# 03-CameraSensor.net
KiCad netlist of a schematic drawn in Altium Designer
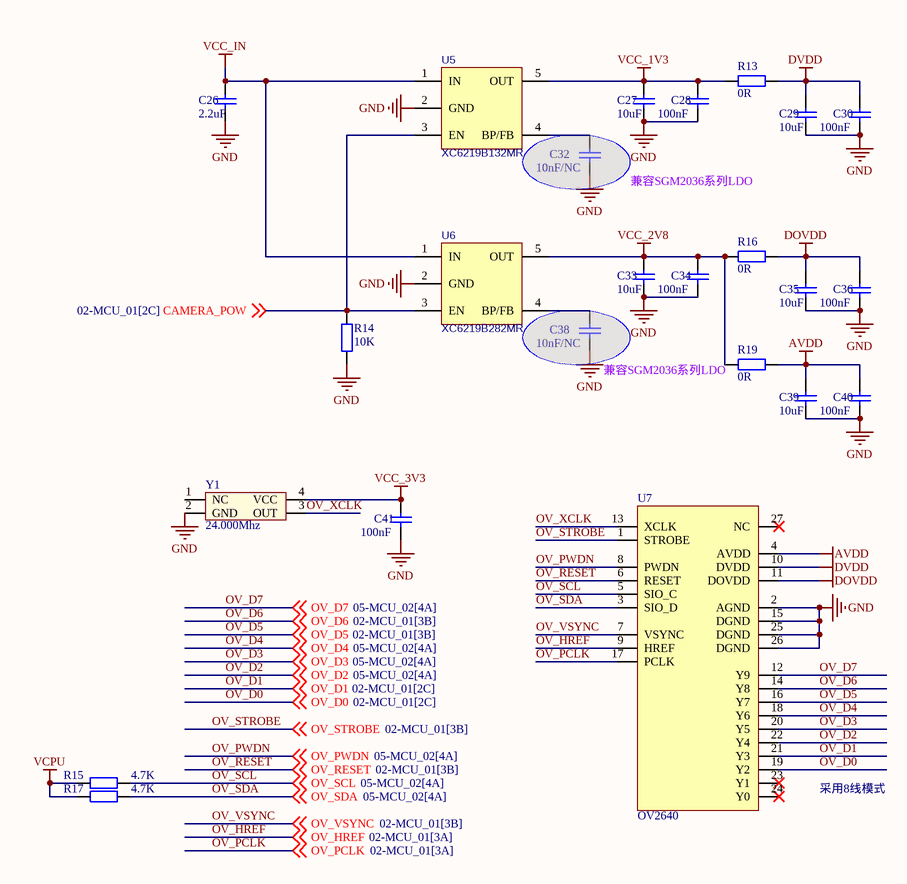
[diagram p0: 03-CameraSensor.SchDoc]

(export (version "E")
  (design (tool "Eeschema 10.0.6"))
  (components
    (comp (ref "C26")
      (value "2.2uF")
      (footprint "C0603_M")
      (description "贴片电容/MLCC电容")
      (libsource (lib "0.1 - 电阻-电容-电感-保险丝-晶振-晶体-磁珠-电位器-法拉电容-馈通电容") (part "C"))
    )
    (comp (ref "C27")
      (value "10uF")
      (footprint "C0603_M")
      (description "贴片电容/MLCC电容")
      (libsource (lib "0.1 - 电阻-电容-电感-保险丝-晶振-晶体-磁珠-电位器-法拉电容-馈通电容") (part "C"))
    )
    (comp (ref "C28")
      (value "100nF")
      (footprint "C0603_M")
      (description "贴片电容/MLCC电容")
      (libsource (lib "0.1 - 电阻-电容-电感-保险丝-晶振-晶体-磁珠-电位器-法拉电容-馈通电容") (part "C"))
    )
    (comp (ref "C29")
      (value "10uF")
      (footprint "C0603_M")
      (description "贴片电容/MLCC电容")
      (libsource (lib "0.1 - 电阻-电容-电感-保险丝-晶振-晶体-磁珠-电位器-法拉电容-馈通电容") (part "C"))
    )
    (comp (ref "C30")
      (value "100nF")
      (footprint "C0603_M")
      (description "贴片电容/MLCC电容")
      (libsource (lib "0.1 - 电阻-电容-电感-保险丝-晶振-晶体-磁珠-电位器-法拉电容-馈通电容") (part "C"))
    )
    (comp (ref "C32")
      (value "10nF/NC")
      (footprint "C0603_M")
      (description "贴片电容/MLCC电容")
      (libsource (lib "0.1 - 电阻-电容-电感-保险丝-晶振-晶体-磁珠-电位器-法拉电容-馈通电容") (part "C"))
    )
    (comp (ref "C33")
      (value "10uF")
      (footprint "C0603_M")
      (description "贴片电容/MLCC电容")
      (libsource (lib "0.1 - 电阻-电容-电感-保险丝-晶振-晶体-磁珠-电位器-法拉电容-馈通电容") (part "C"))
    )
    (comp (ref "C34")
      (value "100nF")
      (footprint "C0603_M")
      (description "贴片电容/MLCC电容")
      (libsource (lib "0.1 - 电阻-电容-电感-保险丝-晶振-晶体-磁珠-电位器-法拉电容-馈通电容") (part "C"))
    )
    (comp (ref "C35")
      (value "10uF")
      (footprint "C0603_M")
      (description "贴片电容/MLCC电容")
      (libsource (lib "0.1 - 电阻-电容-电感-保险丝-晶振-晶体-磁珠-电位器-法拉电容-馈通电容") (part "C"))
    )
    (comp (ref "C36")
      (value "100nF")
      (footprint "C0603_M")
      (description "贴片电容/MLCC电容")
      (libsource (lib "0.1 - 电阻-电容-电感-保险丝-晶振-晶体-磁珠-电位器-法拉电容-馈通电容") (part "C"))
    )
    (comp (ref "C38")
      (value "10nF/NC")
      (footprint "C0603_M")
      (description "贴片电容/MLCC电容")
      (libsource (lib "0.1 - 电阻-电容-电感-保险丝-晶振-晶体-磁珠-电位器-法拉电容-馈通电容") (part "C"))
    )
    (comp (ref "C39")
      (value "10uF")
      (footprint "C0603_M")
      (description "贴片电容/MLCC电容")
      (libsource (lib "0.1 - 电阻-电容-电感-保险丝-晶振-晶体-磁珠-电位器-法拉电容-馈通电容") (part "C"))
    )
    (comp (ref "C40")
      (value "100nF")
      (footprint "C0603_M")
      (description "贴片电容/MLCC电容")
      (libsource (lib "0.1 - 电阻-电容-电感-保险丝-晶振-晶体-磁珠-电位器-法拉电容-馈通电容") (part "C"))
    )
    (comp (ref "C41")
      (value "100nF")
      (footprint "C0603_M")
      (description "贴片电容/MLCC电容")
      (libsource (lib "0.1 - 电阻-电容-电感-保险丝-晶振-晶体-磁珠-电位器-法拉电容-馈通电容") (part "C"))
    )
    (comp (ref "R13")
      (value "0R")
      (footprint "R0603_M")
      (description "贴片电阻")
      (libsource (lib "0.1 - 电阻-电容-电感-保险丝-晶振-晶体-磁珠-电位器-法拉电容-馈通电容") (part "R"))
    )
    (comp (ref "R14")
      (value "10K")
      (footprint "R0603_M")
      (description "贴片电阻")
      (libsource (lib "0.1 - 电阻-电容-电感-保险丝-晶振-晶体-磁珠-电位器-法拉电容-馈通电容") (part "R"))
    )
    (comp (ref "R15")
      (value "4.7K")
      (footprint "R0402_M")
      (description "贴片电阻")
      (libsource (lib "0.1 - 电阻-电容-电感-保险丝-晶振-晶体-磁珠-电位器-法拉电容-馈通电容") (part "R"))
    )
    (comp (ref "R16")
      (value "0R")
      (footprint "R0603_M")
      (description "贴片电阻")
      (libsource (lib "0.1 - 电阻-电容-电感-保险丝-晶振-晶体-磁珠-电位器-法拉电容-馈通电容") (part "R"))
    )
    (comp (ref "R17")
      (value "4.7K")
      (footprint "R0402_M")
      (description "贴片电阻")
      (libsource (lib "0.1 - 电阻-电容-电感-保险丝-晶振-晶体-磁珠-电位器-法拉电容-馈通电容") (part "R"))
    )
    (comp (ref "R19")
      (value "0R")
      (footprint "R0603_M")
      (description "贴片电阻")
      (libsource (lib "0.1 - 电阻-电容-电感-保险丝-晶振-晶体-磁珠-电位器-法拉电容-馈通电容") (part "R"))
    )
    (comp (ref "U5")
      (value "XC6219B132MR")
      (footprint "SOT-23-5")
      (description "LDO 1.8V/0.3A")
      (libsource (lib "0.7 - 电源类芯片") (part "SGM2019-1.8YN5G"))
    )
    (comp (ref "U6")
      (value "XC6219B282MR")
      (footprint "SOT-23-5")
      (description "LDO 1.8V/0.3A")
      (libsource (lib "0.7 - 电源类芯片") (part "SGM2019-1.8YN5G"))
    )
    (comp (ref "U7")
      (value "OV2640")
      (footprint "OV2640-24")
      (libsource (lib "ATK-OV2640 V2.2") (part "OV2640"))
    )
    (comp (ref "Y1")
      (value "24.000Mhz")
      (footprint "XTAL3225")
      (description "有源晶振")
      (libsource (lib "ATK-OV2640 V2.2") (part "XTAL_S"))
    )
  )
  (nets
    (net (code "1") (name "/OV_XCLK") (class "Default")
      (node (ref "U7") (pin "13") (pinfunction "XCLK_13") (pintype "passive"))
      (node (ref "Y1") (pin "3") (pinfunction "OUT_3") (pintype "passive"))
    )
    (net (code "2") (name "AVDD") (class "Default")
      (node (ref "C39") (pin "2") (pinfunction "2_2") (pintype "passive"))
      (node (ref "C40") (pin "2") (pinfunction "2_2") (pintype "passive"))
      (node (ref "R19") (pin "2") (pinfunction "2_2") (pintype "passive"))
      (node (ref "U7") (pin "4") (pinfunction "AVDD_4") (pintype "passive"))
    )
    (net (code "3") (name "CAMERA_POW") (class "Default")
      (node (ref "R14") (pin "2") (pinfunction "2_2") (pintype "passive"))
      (node (ref "U5") (pin "3") (pinfunction "EN_3") (pintype "passive"))
      (node (ref "U6") (pin "3") (pinfunction "EN_3") (pintype "passive"))
    )
    (net (code "4") (name "DOVDD") (class "Default")
      (node (ref "C35") (pin "2") (pinfunction "2_2") (pintype "passive"))
      (node (ref "C36") (pin "2") (pinfunction "2_2") (pintype "passive"))
      (node (ref "R16") (pin "2") (pinfunction "2_2") (pintype "passive"))
      (node (ref "U7") (pin "11") (pinfunction "DOVDD_11") (pintype "passive"))
    )
    (net (code "5") (name "DVDD") (class "Default")
      (node (ref "C29") (pin "2") (pinfunction "2_2") (pintype "passive"))
      (node (ref "C30") (pin "2") (pinfunction "2_2") (pintype "passive"))
      (node (ref "R13") (pin "2") (pinfunction "2_2") (pintype "passive"))
      (node (ref "U7") (pin "10") (pinfunction "DVDD_10") (pintype "passive"))
    )
    (net (code "6") (name "GND") (class "Default")
      (node (ref "C26") (pin "1") (pinfunction "1_1") (pintype "passive"))
      (node (ref "C27") (pin "1") (pinfunction "1_1") (pintype "passive"))
      (node (ref "C28") (pin "1") (pinfunction "1_1") (pintype "passive"))
      (node (ref "C29") (pin "1") (pinfunction "1_1") (pintype "passive"))
      (node (ref "C30") (pin "1") (pinfunction "1_1") (pintype "passive"))
      (node (ref "C32") (pin "1") (pinfunction "1_1") (pintype "passive"))
      (node (ref "C33") (pin "1") (pinfunction "1_1") (pintype "passive"))
      (node (ref "C34") (pin "1") (pinfunction "1_1") (pintype "passive"))
      (node (ref "C35") (pin "1") (pinfunction "1_1") (pintype "passive"))
      (node (ref "C36") (pin "1") (pinfunction "1_1") (pintype "passive"))
      (node (ref "C38") (pin "1") (pinfunction "1_1") (pintype "passive"))
      (node (ref "C39") (pin "1") (pinfunction "1_1") (pintype "passive"))
      (node (ref "C40") (pin "1") (pinfunction "1_1") (pintype "passive"))
      (node (ref "C41") (pin "1") (pinfunction "1_1") (pintype "passive"))
      (node (ref "R14") (pin "1") (pinfunction "1_1") (pintype "passive"))
      (node (ref "U5") (pin "2") (pinfunction "GND_2") (pintype "passive"))
      (node (ref "U6") (pin "2") (pinfunction "GND_2") (pintype "passive"))
      (node (ref "U7") (pin "15") (pinfunction "DGND_15") (pintype "passive"))
      (node (ref "U7") (pin "2") (pinfunction "AGND_2") (pintype "passive"))
      (node (ref "U7") (pin "25") (pinfunction "DGND_25") (pintype "passive"))
      (node (ref "U7") (pin "26") (pinfunction "DGND_26") (pintype "passive"))
      (node (ref "Y1") (pin "2") (pinfunction "GND_2") (pintype "passive"))
    )
    (net (code "7") (name "Net-(U5-BP{slash}FB)") (class "Default")
      (node (ref "C32") (pin "2") (pinfunction "2_2") (pintype "passive"))
      (node (ref "U5") (pin "4") (pinfunction "BP/FB_4") (pintype "passive"))
    )
    (net (code "8") (name "Net-(U6-BP{slash}FB)") (class "Default")
      (node (ref "C38") (pin "2") (pinfunction "2_2") (pintype "passive"))
      (node (ref "U6") (pin "4") (pinfunction "BP/FB_4") (pintype "passive"))
    )
    (net (code "9") (name "OV_D0") (class "Default")
      (node (ref "U7") (pin "19") (pinfunction "Y2_19") (pintype "passive"))
    )
    (net (code "10") (name "OV_D1") (class "Default")
      (node (ref "U7") (pin "21") (pinfunction "Y3_21") (pintype "passive"))
    )
    (net (code "11") (name "OV_D2") (class "Default")
      (node (ref "U7") (pin "22") (pinfunction "Y4_22") (pintype "passive"))
    )
    (net (code "12") (name "OV_D3") (class "Default")
      (node (ref "U7") (pin "20") (pinfunction "Y5_20") (pintype "passive"))
    )
    (net (code "13") (name "OV_D4") (class "Default")
      (node (ref "U7") (pin "18") (pinfunction "Y6_18") (pintype "passive"))
    )
    (net (code "14") (name "OV_D5") (class "Default")
      (node (ref "U7") (pin "16") (pinfunction "Y7_16") (pintype "passive"))
    )
    (net (code "15") (name "OV_D6") (class "Default")
      (node (ref "U7") (pin "14") (pinfunction "Y8_14") (pintype "passive"))
    )
    (net (code "16") (name "OV_D7") (class "Default")
      (node (ref "U7") (pin "12") (pinfunction "Y9_12") (pintype "passive"))
    )
    (net (code "17") (name "OV_HREF") (class "Default")
      (node (ref "U7") (pin "9") (pinfunction "HREF_9") (pintype "passive"))
    )
    (net (code "18") (name "OV_PCLK") (class "Default")
      (node (ref "U7") (pin "17") (pinfunction "PCLK_17") (pintype "passive"))
    )
    (net (code "19") (name "OV_PWDN") (class "Default")
      (node (ref "U7") (pin "8") (pinfunction "PWDN_8") (pintype "passive"))
    )
    (net (code "20") (name "OV_RESET") (class "Default")
      (node (ref "U7") (pin "6") (pinfunction "RESET_6") (pintype "passive"))
    )
    (net (code "21") (name "OV_SCL") (class "Default")
      (node (ref "R15") (pin "1") (pinfunction "1_1") (pintype "passive"))
      (node (ref "U7") (pin "5") (pinfunction "SIO_C_5") (pintype "passive"))
    )
    (net (code "22") (name "OV_SDA") (class "Default")
      (node (ref "R17") (pin "1") (pinfunction "1_1") (pintype "passive"))
      (node (ref "U7") (pin "3") (pinfunction "SIO_D_3") (pintype "passive"))
    )
    (net (code "23") (name "OV_STROBE") (class "Default")
      (node (ref "U7") (pin "1") (pinfunction "STROBE_1") (pintype "passive"))
    )
    (net (code "24") (name "OV_VSYNC") (class "Default")
      (node (ref "U7") (pin "7") (pinfunction "VSYNC_7") (pintype "passive"))
    )
    (net (code "25") (name "VCC_1V3") (class "Default")
      (node (ref "C27") (pin "2") (pinfunction "2_2") (pintype "passive"))
      (node (ref "C28") (pin "2") (pinfunction "2_2") (pintype "passive"))
      (node (ref "R13") (pin "1") (pinfunction "1_1") (pintype "passive"))
      (node (ref "U5") (pin "5") (pinfunction "OUT_5") (pintype "passive"))
    )
    (net (code "26") (name "VCC_2V8") (class "Default")
      (node (ref "C33") (pin "2") (pinfunction "2_2") (pintype "passive"))
      (node (ref "C34") (pin "2") (pinfunction "2_2") (pintype "passive"))
      (node (ref "R16") (pin "1") (pinfunction "1_1") (pintype "passive"))
      (node (ref "R19") (pin "1") (pinfunction "1_1") (pintype "passive"))
      (node (ref "U6") (pin "5") (pinfunction "OUT_5") (pintype "passive"))
    )
    (net (code "27") (name "VCC_3V3") (class "Default")
      (node (ref "C41") (pin "2") (pinfunction "2_2") (pintype "passive"))
      (node (ref "Y1") (pin "4") (pinfunction "VCC_4") (pintype "passive"))
    )
    (net (code "28") (name "VCC_IN") (class "Default")
      (node (ref "C26") (pin "2") (pinfunction "2_2") (pintype "passive"))
      (node (ref "U5") (pin "1") (pinfunction "IN_1") (pintype "passive"))
      (node (ref "U6") (pin "1") (pinfunction "IN_1") (pintype "passive"))
    )
    (net (code "29") (name "VCPU") (class "Default")
      (node (ref "R15") (pin "2") (pinfunction "2_2") (pintype "passive"))
      (node (ref "R17") (pin "2") (pinfunction "2_2") (pintype "passive"))
    )
    (net (code "30") (name "unconnected-(U7-NC-Pad27)") (class "Default")
      (node (ref "U7") (pin "27") (pinfunction "NC_27") (pintype "passive+no_connect"))
    )
    (net (code "31") (name "unconnected-(U7-Y0-Pad24)") (class "Default")
      (node (ref "U7") (pin "24") (pinfunction "Y0_24") (pintype "passive+no_connect"))
    )
    (net (code "32") (name "unconnected-(U7-Y1-Pad23)") (class "Default")
      (node (ref "U7") (pin "23") (pinfunction "Y1_23") (pintype "passive+no_connect"))
    )
    (net (code "33") (name "unconnected-(Y1-NC-Pad1)") (class "Default")
      (node (ref "Y1") (pin "1") (pinfunction "NC_1") (pintype "passive"))
    )
  )
)
